# BD.net
KiCad netlist of a schematic drawn in EAGLE
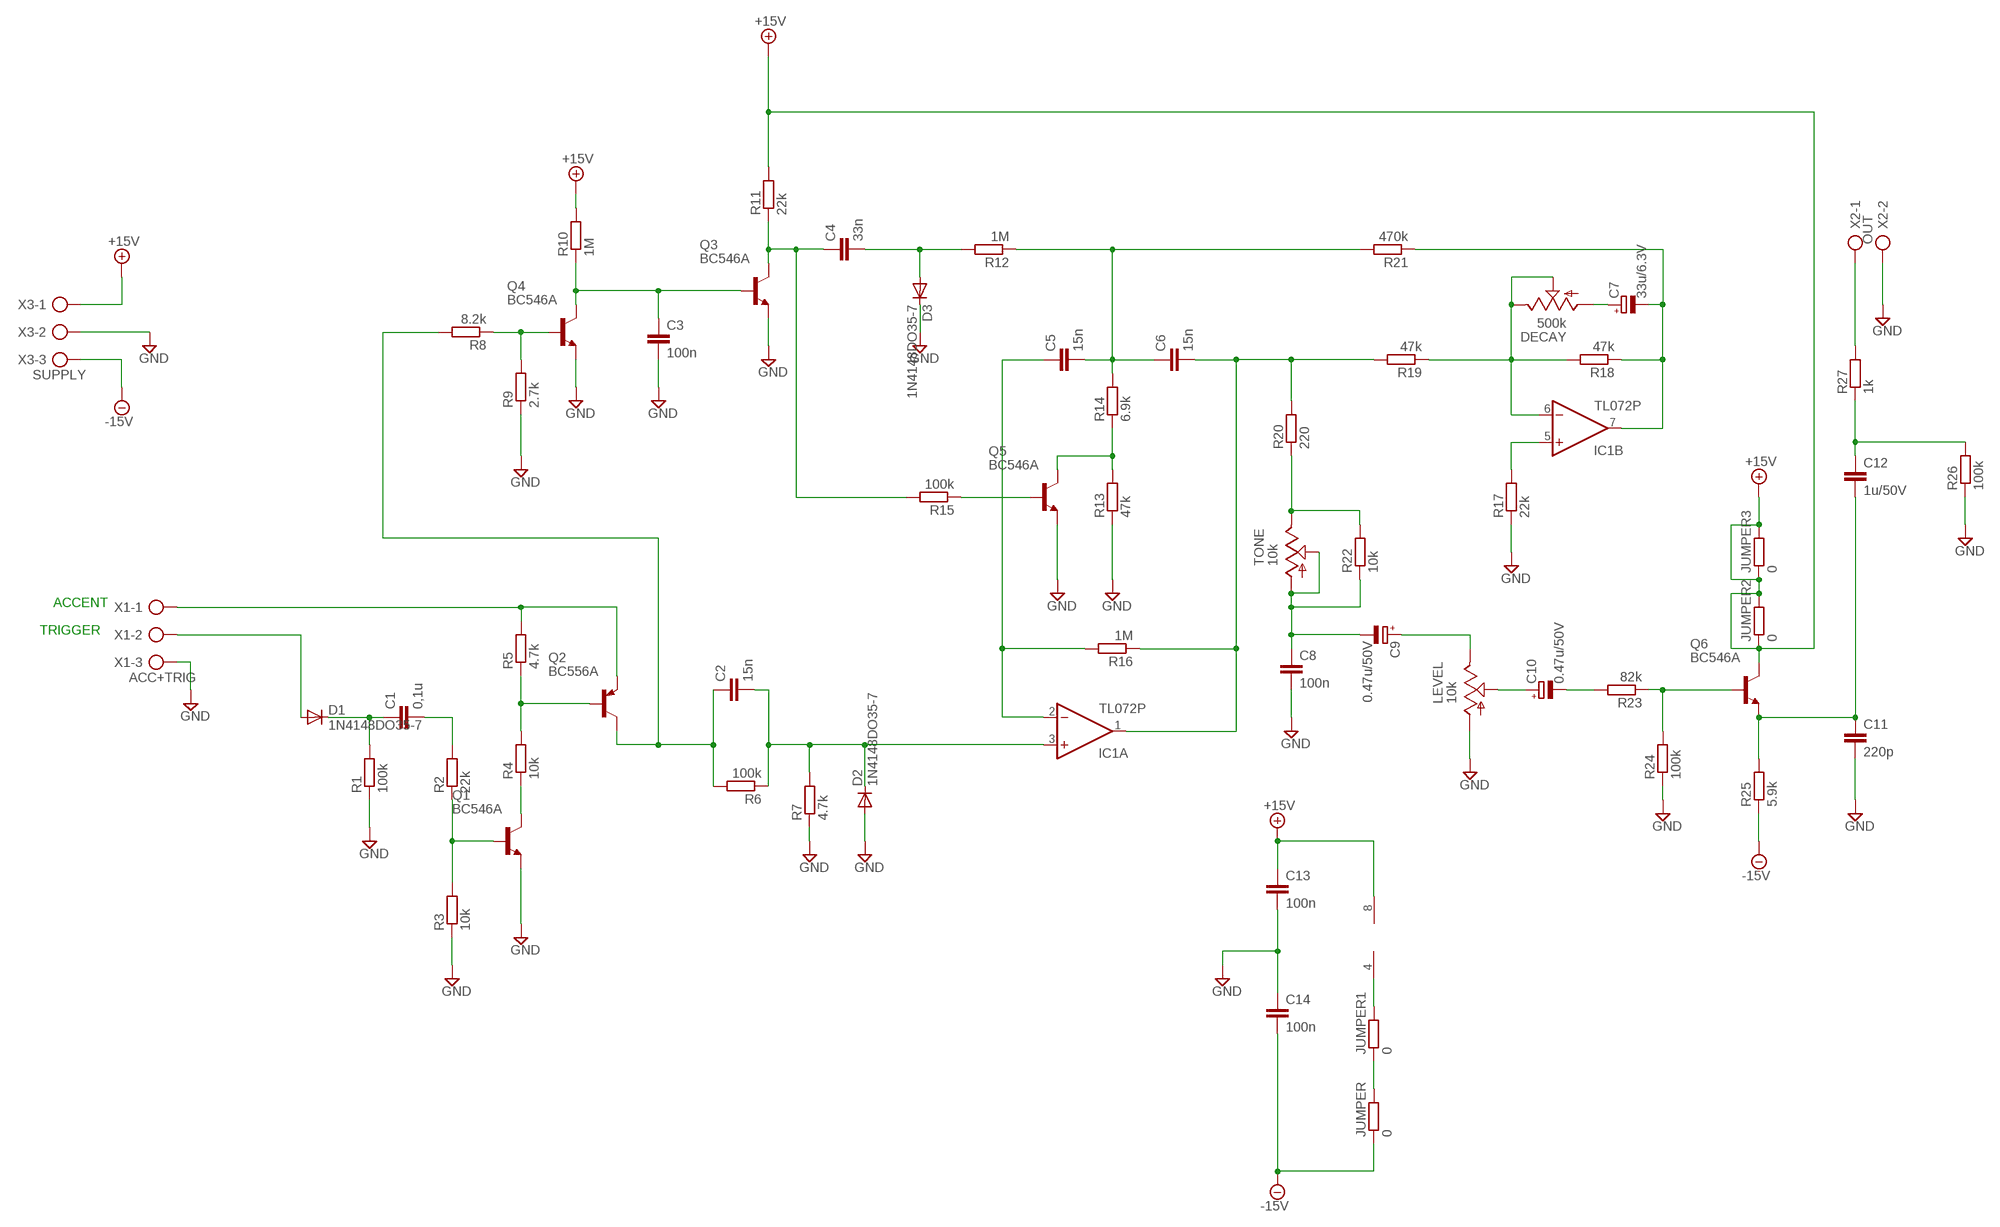
[diagram p0: schematic, sheet 1]

(export (version "E")
  (design (tool "Eeschema 10.0.6"))
  (components
    (comp (ref "C1")
      (value "0,1u")
      (footprint "eagle-import:C075-042X103")
      (libsource (lib "eagle-import") (part "C-EU075-042X103"))
    )
    (comp (ref "C2")
      (value "15n")
      (footprint "eagle-import:C075-042X103")
      (libsource (lib "eagle-import") (part "C-EU075-042X103"))
    )
    (comp (ref "C3")
      (value "100n")
      (footprint "eagle-import:C075-042X103")
      (libsource (lib "eagle-import") (part "C-EU075-042X103"))
    )
    (comp (ref "C4")
      (value "33n")
      (footprint "eagle-import:C075-042X103")
      (libsource (lib "eagle-import") (part "C-EU075-042X103"))
    )
    (comp (ref "C5")
      (value "15n")
      (footprint "eagle-import:C075-042X103")
      (libsource (lib "eagle-import") (part "C-EU075-042X103"))
    )
    (comp (ref "C6")
      (value "15n")
      (footprint "eagle-import:C075-042X103")
      (libsource (lib "eagle-import") (part "C-EU075-042X103"))
    )
    (comp (ref "C7")
      (value "33u/6.3V")
      (footprint "eagle-import:E2-5")
      (libsource (lib "eagle-import") (part "CPOL-EUE2-5"))
    )
    (comp (ref "C8")
      (value "100n")
      (footprint "eagle-import:C075-042X103")
      (libsource (lib "eagle-import") (part "C-EU075-042X103"))
    )
    (comp (ref "C9")
      (value "0.47u/50V")
      (footprint "eagle-import:E2-5")
      (libsource (lib "eagle-import") (part "CPOL-EUE2-5"))
    )
    (comp (ref "C10")
      (value "0.47u/50V")
      (footprint "eagle-import:E2-5")
      (libsource (lib "eagle-import") (part "CPOL-EUE2-5"))
    )
    (comp (ref "C11")
      (value "220p")
      (footprint "eagle-import:C075-042X103")
      (libsource (lib "eagle-import") (part "C-EU075-042X103"))
    )
    (comp (ref "C12")
      (value "1u/50V")
      (footprint "eagle-import:C075-042X103")
      (libsource (lib "eagle-import") (part "C-EU075-042X103"))
    )
    (comp (ref "C13")
      (value "100n")
      (footprint "eagle-import:C075-042X103")
      (libsource (lib "eagle-import") (part "C-EU075-042X103"))
    )
    (comp (ref "C14")
      (value "100n")
      (footprint "eagle-import:C075-042X103")
      (libsource (lib "eagle-import") (part "C-EU075-042X103"))
    )
    (comp (ref "D1")
      (value "1N4148DO35-7")
      (footprint "eagle-import:DO35-7")
      (libsource (lib "eagle-import") (part "1N4148DO35-7"))
    )
    (comp (ref "D2")
      (value "1N4148DO35-7")
      (footprint "eagle-import:DO35-7")
      (libsource (lib "eagle-import") (part "1N4148DO35-7"))
    )
    (comp (ref "D3")
      (value "1N4148DO35-7")
      (footprint "eagle-import:DO35-7")
      (libsource (lib "eagle-import") (part "1N4148DO35-7"))
    )
    (comp (ref "DECAY")
      (value "500k")
      (footprint "eagle-import:CA9H")
      (libsource (lib "eagle-import") (part "TRIM_US-CA9H"))
    )
    (comp (ref "IC1")
      (value "TL072P")
      (footprint "eagle-import:DIL08")
      (libsource (lib "eagle-import") (part "TL072P"))
    )
    (comp (ref "JUMPER")
      (value "0")
      (footprint "eagle-import:0207_10")
      (libsource (lib "eagle-import") (part "R-EU_0207/10"))
    )
    (comp (ref "JUMPER1")
      (value "0")
      (footprint "eagle-import:0207_10")
      (libsource (lib "eagle-import") (part "R-EU_0207/10"))
    )
    (comp (ref "JUMPER2")
      (value "0")
      (footprint "eagle-import:0207_10")
      (libsource (lib "eagle-import") (part "R-EU_0207/10"))
    )
    (comp (ref "JUMPER3")
      (value "0")
      (footprint "eagle-import:0207_10")
      (libsource (lib "eagle-import") (part "R-EU_0207/10"))
    )
    (comp (ref "LEVEL")
      (value "10k")
      (footprint "eagle-import:CA9H")
      (libsource (lib "eagle-import") (part "TRIM_US-CA9H"))
    )
    (comp (ref "Q1")
      (value "BC546A")
      (footprint "eagle-import:TO92-EBC")
      (libsource (lib "eagle-import") (part "BC546A"))
    )
    (comp (ref "Q2")
      (value "BC556A")
      (footprint "eagle-import:TO92-EBC")
      (libsource (lib "eagle-import") (part "BC556A"))
    )
    (comp (ref "Q3")
      (value "BC546A")
      (footprint "eagle-import:TO92-EBC")
      (libsource (lib "eagle-import") (part "BC546A"))
    )
    (comp (ref "Q4")
      (value "BC546A")
      (footprint "eagle-import:TO92-EBC")
      (libsource (lib "eagle-import") (part "BC546A"))
    )
    (comp (ref "Q5")
      (value "BC546A")
      (footprint "eagle-import:TO92-EBC")
      (libsource (lib "eagle-import") (part "BC546A"))
    )
    (comp (ref "Q6")
      (value "BC546A")
      (footprint "eagle-import:TO92-EBC")
      (libsource (lib "eagle-import") (part "BC546A"))
    )
    (comp (ref "R1")
      (value "100k")
      (footprint "eagle-import:0207_10")
      (libsource (lib "eagle-import") (part "R-EU_0207/10"))
    )
    (comp (ref "R2")
      (value "22k")
      (footprint "eagle-import:0207_10")
      (libsource (lib "eagle-import") (part "R-EU_0207/10"))
    )
    (comp (ref "R3")
      (value "10k")
      (footprint "eagle-import:0207_10")
      (libsource (lib "eagle-import") (part "R-EU_0207/10"))
    )
    (comp (ref "R4")
      (value "10k")
      (footprint "eagle-import:0207_10")
      (libsource (lib "eagle-import") (part "R-EU_0207/10"))
    )
    (comp (ref "R5")
      (value "4.7k")
      (footprint "eagle-import:0207_10")
      (libsource (lib "eagle-import") (part "R-EU_0207/10"))
    )
    (comp (ref "R6")
      (value "100k")
      (footprint "eagle-import:0207_10")
      (libsource (lib "eagle-import") (part "R-EU_0207/10"))
    )
    (comp (ref "R7")
      (value "4.7k")
      (footprint "eagle-import:0207_10")
      (libsource (lib "eagle-import") (part "R-EU_0207/10"))
    )
    (comp (ref "R8")
      (value "8.2k")
      (footprint "eagle-import:0207_10")
      (libsource (lib "eagle-import") (part "R-EU_0207/10"))
    )
    (comp (ref "R9")
      (value "2.7k")
      (footprint "eagle-import:0207_10")
      (libsource (lib "eagle-import") (part "R-EU_0207/10"))
    )
    (comp (ref "R10")
      (value "1M")
      (footprint "eagle-import:0207_10")
      (libsource (lib "eagle-import") (part "R-EU_0207/10"))
    )
    (comp (ref "R11")
      (value "22k")
      (footprint "eagle-import:0207_10")
      (libsource (lib "eagle-import") (part "R-EU_0207/10"))
    )
    (comp (ref "R12")
      (value "1M")
      (footprint "eagle-import:0207_10")
      (libsource (lib "eagle-import") (part "R-EU_0207/10"))
    )
    (comp (ref "R13")
      (value "47k")
      (footprint "eagle-import:0207_10")
      (libsource (lib "eagle-import") (part "R-EU_0207/10"))
    )
    (comp (ref "R14")
      (value "6.9k")
      (footprint "eagle-import:0207_10")
      (libsource (lib "eagle-import") (part "R-EU_0207/10"))
    )
    (comp (ref "R15")
      (value "100k")
      (footprint "eagle-import:0207_10")
      (libsource (lib "eagle-import") (part "R-EU_0207/10"))
    )
    (comp (ref "R16")
      (value "1M")
      (footprint "eagle-import:0207_10")
      (libsource (lib "eagle-import") (part "R-EU_0207/10"))
    )
    (comp (ref "R17")
      (value "22k")
      (footprint "eagle-import:0207_10")
      (libsource (lib "eagle-import") (part "R-EU_0207/10"))
    )
    (comp (ref "R18")
      (value "47k")
      (footprint "eagle-import:0207_10")
      (libsource (lib "eagle-import") (part "R-EU_0207/10"))
    )
    (comp (ref "R19")
      (value "47k")
      (footprint "eagle-import:0207_10")
      (libsource (lib "eagle-import") (part "R-EU_0207/10"))
    )
    (comp (ref "R20")
      (value "220")
      (footprint "eagle-import:0207_10")
      (libsource (lib "eagle-import") (part "R-EU_0207/10"))
    )
    (comp (ref "R21")
      (value "470k")
      (footprint "eagle-import:0207_10")
      (libsource (lib "eagle-import") (part "R-EU_0207/10"))
    )
    (comp (ref "R22")
      (value "10k")
      (footprint "eagle-import:0207_10")
      (libsource (lib "eagle-import") (part "R-EU_0207/10"))
    )
    (comp (ref "R23")
      (value "82k")
      (footprint "eagle-import:0207_10")
      (libsource (lib "eagle-import") (part "R-EU_0207/10"))
    )
    (comp (ref "R24")
      (value "100k")
      (footprint "eagle-import:0207_10")
      (libsource (lib "eagle-import") (part "R-EU_0207/10"))
    )
    (comp (ref "R25")
      (value "5.9k")
      (footprint "eagle-import:0207_10")
      (libsource (lib "eagle-import") (part "R-EU_0207/10"))
    )
    (comp (ref "R26")
      (value "100k")
      (footprint "eagle-import:0207_10")
      (libsource (lib "eagle-import") (part "R-EU_0207/10"))
    )
    (comp (ref "R27")
      (value "1k")
      (footprint "eagle-import:0207_10")
      (libsource (lib "eagle-import") (part "R-EU_0207/10"))
    )
    (comp (ref "TONE")
      (value "10k")
      (footprint "eagle-import:CA9H")
      (libsource (lib "eagle-import") (part "TRIM_US-CA9H"))
    )
    (comp (ref "X1")
      (value "ACC+TRIG")
      (footprint "eagle-import:AK300_3")
      (libsource (lib "eagle-import") (part "AK300/3"))
    )
    (comp (ref "X2")
      (value "OUT")
      (footprint "eagle-import:AK300_2")
      (libsource (lib "eagle-import") (part "AK300/2"))
    )
    (comp (ref "X3")
      (value "SUPPLY")
      (footprint "eagle-import:AK300_3")
      (libsource (lib "eagle-import") (part "AK300/3"))
    )
  )
  (nets
    (net (code "1") (name "+15V") (class "Default")
      (node (ref "C13") (pin "1") (pinfunction "1_1") (pintype "passive"))
      (node (ref "IC1") (pin "8") (pinfunction "V+_8") (pintype "power_in"))
      (node (ref "JUMPER2") (pin "1") (pinfunction "1_1") (pintype "passive"))
      (node (ref "JUMPER2") (pin "2") (pinfunction "2_2") (pintype "passive"))
      (node (ref "JUMPER3") (pin "1") (pinfunction "1_1") (pintype "passive"))
      (node (ref "JUMPER3") (pin "2") (pinfunction "2_2") (pintype "passive"))
      (node (ref "Q6") (pin "C") (pinfunction "C_C") (pintype "passive"))
      (node (ref "R10") (pin "2") (pinfunction "2_2") (pintype "passive"))
      (node (ref "R11") (pin "2") (pinfunction "2_2") (pintype "passive"))
      (node (ref "X3") (pin "1") (pinfunction "KL_1") (pintype "passive"))
    )
    (net (code "2") (name "-15V") (class "Default")
      (node (ref "C14") (pin "2") (pinfunction "2_2") (pintype "passive"))
      (node (ref "JUMPER") (pin "1") (pinfunction "1_1") (pintype "passive"))
      (node (ref "R25") (pin "1") (pinfunction "1_1") (pintype "passive"))
      (node (ref "X3") (pin "3") (pinfunction "KL_3") (pintype "passive"))
    )
    (net (code "3") (name "GND") (class "Default")
      (node (ref "C11") (pin "2") (pinfunction "2_2") (pintype "passive"))
      (node (ref "C13") (pin "2") (pinfunction "2_2") (pintype "passive"))
      (node (ref "C14") (pin "1") (pinfunction "1_1") (pintype "passive"))
      (node (ref "C3") (pin "2") (pinfunction "2_2") (pintype "passive"))
      (node (ref "C8") (pin "2") (pinfunction "2_2") (pintype "passive"))
      (node (ref "D2") (pin "A") (pinfunction "A_A") (pintype "passive"))
      (node (ref "D3") (pin "C") (pinfunction "C_C") (pintype "passive"))
      (node (ref "LEVEL") (pin "A") (pinfunction "A_A") (pintype "passive"))
      (node (ref "Q1") (pin "E") (pinfunction "E_E") (pintype "passive"))
      (node (ref "Q3") (pin "E") (pinfunction "E_E") (pintype "passive"))
      (node (ref "Q4") (pin "E") (pinfunction "E_E") (pintype "passive"))
      (node (ref "Q5") (pin "E") (pinfunction "E_E") (pintype "passive"))
      (node (ref "R1") (pin "1") (pinfunction "1_1") (pintype "passive"))
      (node (ref "R13") (pin "1") (pinfunction "1_1") (pintype "passive"))
      (node (ref "R17") (pin "1") (pinfunction "1_1") (pintype "passive"))
      (node (ref "R24") (pin "1") (pinfunction "1_1") (pintype "passive"))
      (node (ref "R26") (pin "1") (pinfunction "1_1") (pintype "passive"))
      (node (ref "R3") (pin "1") (pinfunction "1_1") (pintype "passive"))
      (node (ref "R7") (pin "1") (pinfunction "1_1") (pintype "passive"))
      (node (ref "R9") (pin "1") (pinfunction "1_1") (pintype "passive"))
      (node (ref "X1") (pin "3") (pinfunction "KL_3") (pintype "passive"))
      (node (ref "X2") (pin "2") (pinfunction "KL_2") (pintype "passive"))
      (node (ref "X3") (pin "2") (pinfunction "KL_2") (pintype "passive"))
    )
    (net (code "4") (name "Net-(C1-Pad1)") (class "Default")
      (node (ref "C1") (pin "1") (pinfunction "1_1") (pintype "passive"))
      (node (ref "D1") (pin "C") (pinfunction "C_C") (pintype "passive"))
      (node (ref "R1") (pin "2") (pinfunction "2_2") (pintype "passive"))
    )
    (net (code "5") (name "Net-(C1-Pad2)") (class "Default")
      (node (ref "C1") (pin "2") (pinfunction "2_2") (pintype "passive"))
      (node (ref "R2") (pin "2") (pinfunction "2_2") (pintype "passive"))
    )
    (net (code "6") (name "Net-(C2-Pad1)") (class "Default")
      (node (ref "C2") (pin "1") (pinfunction "1_1") (pintype "passive"))
      (node (ref "Q2") (pin "C") (pinfunction "C_C") (pintype "passive"))
      (node (ref "R6") (pin "2") (pinfunction "2_2") (pintype "passive"))
      (node (ref "R8") (pin "2") (pinfunction "2_2") (pintype "passive"))
    )
    (net (code "7") (name "Net-(C3-Pad1)") (class "Default")
      (node (ref "C3") (pin "1") (pinfunction "1_1") (pintype "passive"))
      (node (ref "Q3") (pin "B") (pinfunction "B_B") (pintype "passive"))
      (node (ref "Q4") (pin "C") (pinfunction "C_C") (pintype "passive"))
      (node (ref "R10") (pin "1") (pinfunction "1_1") (pintype "passive"))
    )
    (net (code "8") (name "Net-(C4-Pad1)") (class "Default")
      (node (ref "C4") (pin "1") (pinfunction "1_1") (pintype "passive"))
      (node (ref "Q3") (pin "C") (pinfunction "C_C") (pintype "passive"))
      (node (ref "R11") (pin "1") (pinfunction "1_1") (pintype "passive"))
      (node (ref "R15") (pin "2") (pinfunction "2_2") (pintype "passive"))
    )
    (net (code "9") (name "Net-(C4-Pad2)") (class "Default")
      (node (ref "C4") (pin "2") (pinfunction "2_2") (pintype "passive"))
      (node (ref "D3") (pin "A") (pinfunction "A_A") (pintype "passive"))
      (node (ref "R12") (pin "2") (pinfunction "2_2") (pintype "passive"))
    )
    (net (code "10") (name "Net-(C5-Pad2)") (class "Default")
      (node (ref "C5") (pin "2") (pinfunction "2_2") (pintype "passive"))
      (node (ref "C6") (pin "1") (pinfunction "1_1") (pintype "passive"))
      (node (ref "R12") (pin "1") (pinfunction "1_1") (pintype "passive"))
      (node (ref "R14") (pin "2") (pinfunction "2_2") (pintype "passive"))
      (node (ref "R21") (pin "2") (pinfunction "2_2") (pintype "passive"))
    )
    (net (code "11") (name "Net-(C7-Pad+)") (class "Default")
      (node (ref "C7") (pin "+") (pinfunction "+_+") (pintype "passive"))
      (node (ref "DECAY") (pin "A") (pinfunction "A_A") (pintype "passive"))
    )
    (net (code "12") (name "Net-(C8-Pad1)") (class "Default")
      (node (ref "C8") (pin "1") (pinfunction "1_1") (pintype "passive"))
      (node (ref "C9") (pin "-") (pinfunction "-_-") (pintype "passive"))
      (node (ref "R22") (pin "1") (pinfunction "1_1") (pintype "passive"))
      (node (ref "TONE") (pin "A") (pinfunction "A_A") (pintype "passive"))
      (node (ref "TONE") (pin "S") (pinfunction "S_S") (pintype "passive"))
    )
    (net (code "13") (name "Net-(C9-Pad+)") (class "Default")
      (node (ref "C9") (pin "+") (pinfunction "+_+") (pintype "passive"))
      (node (ref "LEVEL") (pin "E") (pinfunction "E_E") (pintype "passive"))
    )
    (net (code "14") (name "Net-(C10-Pad+)") (class "Default")
      (node (ref "C10") (pin "+") (pinfunction "+_+") (pintype "passive"))
      (node (ref "LEVEL") (pin "S") (pinfunction "S_S") (pintype "passive"))
    )
    (net (code "15") (name "Net-(C10-Pad-)") (class "Default")
      (node (ref "C10") (pin "-") (pinfunction "-_-") (pintype "passive"))
      (node (ref "R23") (pin "2") (pinfunction "2_2") (pintype "passive"))
    )
    (net (code "16") (name "Net-(C11-Pad1)") (class "Default")
      (node (ref "C11") (pin "1") (pinfunction "1_1") (pintype "passive"))
      (node (ref "C12") (pin "2") (pinfunction "2_2") (pintype "passive"))
      (node (ref "Q6") (pin "E") (pinfunction "E_E") (pintype "passive"))
      (node (ref "R25") (pin "2") (pinfunction "2_2") (pintype "passive"))
    )
    (net (code "17") (name "Net-(C12-Pad1)") (class "Default")
      (node (ref "C12") (pin "1") (pinfunction "1_1") (pintype "passive"))
      (node (ref "R26") (pin "2") (pinfunction "2_2") (pintype "passive"))
      (node (ref "R27") (pin "1") (pinfunction "1_1") (pintype "passive"))
    )
    (net (code "18") (name "Net-(IC1A-+IN)") (class "Default")
      (node (ref "C2") (pin "2") (pinfunction "2_2") (pintype "passive"))
      (node (ref "D2") (pin "C") (pinfunction "C_C") (pintype "passive"))
      (node (ref "IC1") (pin "3") (pinfunction "+IN_3") (pintype "input"))
      (node (ref "R6") (pin "1") (pinfunction "1_1") (pintype "passive"))
      (node (ref "R7") (pin "2") (pinfunction "2_2") (pintype "passive"))
    )
    (net (code "19") (name "Net-(IC1A--IN)") (class "Default")
      (node (ref "C5") (pin "1") (pinfunction "1_1") (pintype "passive"))
      (node (ref "IC1") (pin "2") (pinfunction "-IN_2") (pintype "input"))
      (node (ref "R16") (pin "2") (pinfunction "2_2") (pintype "passive"))
    )
    (net (code "20") (name "Net-(IC1A-OUT)") (class "Default")
      (node (ref "C6") (pin "2") (pinfunction "2_2") (pintype "passive"))
      (node (ref "IC1") (pin "1") (pinfunction "OUT_1") (pintype "output"))
      (node (ref "R16") (pin "1") (pinfunction "1_1") (pintype "passive"))
      (node (ref "R19") (pin "2") (pinfunction "2_2") (pintype "passive"))
      (node (ref "R20") (pin "2") (pinfunction "2_2") (pintype "passive"))
    )
    (net (code "21") (name "Net-(IC1B-+IN)") (class "Default")
      (node (ref "IC1") (pin "5") (pinfunction "+IN_5") (pintype "input"))
      (node (ref "R17") (pin "2") (pinfunction "2_2") (pintype "passive"))
    )
    (net (code "22") (name "Net-(IC1B--IN)") (class "Default")
      (node (ref "DECAY") (pin "E") (pinfunction "E_E") (pintype "passive"))
      (node (ref "DECAY") (pin "S") (pinfunction "S_S") (pintype "passive"))
      (node (ref "IC1") (pin "6") (pinfunction "-IN_6") (pintype "input"))
      (node (ref "R18") (pin "2") (pinfunction "2_2") (pintype "passive"))
      (node (ref "R19") (pin "1") (pinfunction "1_1") (pintype "passive"))
    )
    (net (code "23") (name "Net-(IC1B-OUT)") (class "Default")
      (node (ref "C7") (pin "-") (pinfunction "-_-") (pintype "passive"))
      (node (ref "IC1") (pin "7") (pinfunction "OUT_7") (pintype "output"))
      (node (ref "R18") (pin "1") (pinfunction "1_1") (pintype "passive"))
      (node (ref "R21") (pin "1") (pinfunction "1_1") (pintype "passive"))
    )
    (net (code "24") (name "Net-(IC1C-V-)") (class "Default")
      (node (ref "IC1") (pin "4") (pinfunction "V-_4") (pintype "power_in"))
      (node (ref "JUMPER1") (pin "2") (pinfunction "2_2") (pintype "passive"))
    )
    (net (code "25") (name "Net-(JUMPER-Pad2)") (class "Default")
      (node (ref "JUMPER") (pin "2") (pinfunction "2_2") (pintype "passive"))
      (node (ref "JUMPER1") (pin "1") (pinfunction "1_1") (pintype "passive"))
    )
    (net (code "26") (name "Net-(Q1-PadB)") (class "Default")
      (node (ref "Q1") (pin "B") (pinfunction "B_B") (pintype "passive"))
      (node (ref "R2") (pin "1") (pinfunction "1_1") (pintype "passive"))
      (node (ref "R3") (pin "2") (pinfunction "2_2") (pintype "passive"))
    )
    (net (code "27") (name "Net-(Q1-PadC)") (class "Default")
      (node (ref "Q1") (pin "C") (pinfunction "C_C") (pintype "passive"))
      (node (ref "R4") (pin "1") (pinfunction "1_1") (pintype "passive"))
    )
    (net (code "28") (name "Net-(Q2-PadB)") (class "Default")
      (node (ref "Q2") (pin "B") (pinfunction "B_B") (pintype "passive"))
      (node (ref "R4") (pin "2") (pinfunction "2_2") (pintype "passive"))
      (node (ref "R5") (pin "1") (pinfunction "1_1") (pintype "passive"))
    )
    (net (code "29") (name "Net-(Q4-PadB)") (class "Default")
      (node (ref "Q4") (pin "B") (pinfunction "B_B") (pintype "passive"))
      (node (ref "R8") (pin "1") (pinfunction "1_1") (pintype "passive"))
      (node (ref "R9") (pin "2") (pinfunction "2_2") (pintype "passive"))
    )
    (net (code "30") (name "Net-(Q5-PadB)") (class "Default")
      (node (ref "Q5") (pin "B") (pinfunction "B_B") (pintype "passive"))
      (node (ref "R15") (pin "1") (pinfunction "1_1") (pintype "passive"))
    )
    (net (code "31") (name "Net-(Q5-PadC)") (class "Default")
      (node (ref "Q5") (pin "C") (pinfunction "C_C") (pintype "passive"))
      (node (ref "R13") (pin "2") (pinfunction "2_2") (pintype "passive"))
      (node (ref "R14") (pin "1") (pinfunction "1_1") (pintype "passive"))
    )
    (net (code "32") (name "Net-(Q6-PadB)") (class "Default")
      (node (ref "Q6") (pin "B") (pinfunction "B_B") (pintype "passive"))
      (node (ref "R23") (pin "1") (pinfunction "1_1") (pintype "passive"))
      (node (ref "R24") (pin "2") (pinfunction "2_2") (pintype "passive"))
    )
    (net (code "33") (name "Net-(R20-Pad1)") (class "Default")
      (node (ref "R20") (pin "1") (pinfunction "1_1") (pintype "passive"))
      (node (ref "R22") (pin "2") (pinfunction "2_2") (pintype "passive"))
      (node (ref "TONE") (pin "E") (pinfunction "E_E") (pintype "passive"))
    )
    (net (code "34") (name "Net-(X1A-KL)") (class "Default")
      (node (ref "Q2") (pin "E") (pinfunction "E_E") (pintype "passive"))
      (node (ref "R5") (pin "2") (pinfunction "2_2") (pintype "passive"))
      (node (ref "X1") (pin "1") (pinfunction "KL_1") (pintype "passive"))
    )
    (net (code "35") (name "Net-(X1B-KL)") (class "Default")
      (node (ref "D1") (pin "A") (pinfunction "A_A") (pintype "passive"))
      (node (ref "X1") (pin "2") (pinfunction "KL_2") (pintype "passive"))
    )
    (net (code "36") (name "Net-(X2A-KL)") (class "Default")
      (node (ref "R27") (pin "2") (pinfunction "2_2") (pintype "passive"))
      (node (ref "X2") (pin "1") (pinfunction "KL_1") (pintype "passive"))
    )
  )
)
